# ak8975_i2c.net
KiCad netlist of a schematic drawn in Altium Designer
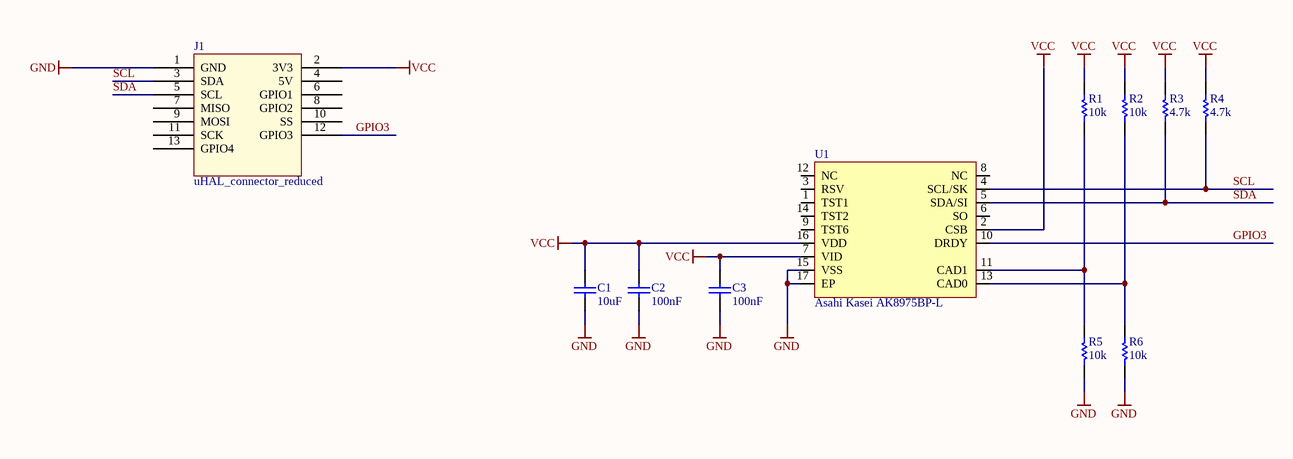
[diagram p0: ak8975_i2c.SchDoc]

(export (version "E")
  (design (tool "Eeschema 10.0.6"))
  (components
    (comp (ref "C1")
      (value "Murata GCM188R71H104KA57D")
      (footprint "CAPC1608X90X35ML10T15")
      (description "CAP CER 0.1UF 50V 10% X7R 0603")
      (fields (field (name "CAPACITANCE") "10uF"))
      (libsource (lib "CommunityVault") (part "CMP-119667-3"))
    )
    (comp (ref "C2")
      (value "Murata GCM188R71H104KA57D")
      (footprint "CAPC1608X90X35ML10T15")
      (description "CAP CER 0.1UF 50V 10% X7R 0603")
      (fields (field (name "CAPACITANCE") "100nF"))
      (libsource (lib "CommunityVault") (part "CMP-119667-3"))
    )
    (comp (ref "C3")
      (value "Murata GCM188R71H104KA57D")
      (footprint "CAPC1608X90X35ML10T15")
      (description "CAP CER 0.1UF 50V 10% X7R 0603")
      (fields (field (name "CAPACITANCE") "100nF"))
      (libsource (lib "CommunityVault") (part "CMP-119667-3"))
    )
    (comp (ref "J1")
      (value "uHAL_connector_reduced")
      (footprint "PCB-45ncoppm4oopozvqifsq-1")
      (description "connector for uHAL with reduced pin number")
      (libsource (lib "CommunityVault") (part "CMP-2q23h2cwhjlfm8s6r7i8-1"))
    )
    (comp (ref "R1")
      (value "10k")
      (footprint "RESC1608X05N")
      (description "RCA Series 0603 0.1 W 0 O Jumper Surface Mount Thick Film Chip Resistor")
      (fields (field (name "MANUFACTURER PART NUMBER") "RCA06030000ZSEA"))
      (libsource (lib "CommunityVault") (part "SYM-31acf99032f6ee6b-1"))
    )
    (comp (ref "R2")
      (value "10k")
      (footprint "RESC1608X05N")
      (description "RCA Series 0603 0.1 W 0 O Jumper Surface Mount Thick Film Chip Resistor")
      (fields (field (name "MANUFACTURER PART NUMBER") "RCA06030000ZSEA"))
      (libsource (lib "CommunityVault") (part "SYM-31acf99032f6ee6b-1"))
    )
    (comp (ref "R3")
      (value "4.7k")
      (footprint "RESC1608X05N")
      (description "RCA Series 0603 0.1 W 0 O Jumper Surface Mount Thick Film Chip Resistor")
      (fields (field (name "MANUFACTURER PART NUMBER") "RCA06030000ZSEA"))
      (libsource (lib "CommunityVault") (part "SYM-31acf99032f6ee6b-1"))
    )
    (comp (ref "R4")
      (value "4.7k")
      (footprint "RESC1608X05N")
      (description "RCA Series 0603 0.1 W 0 O Jumper Surface Mount Thick Film Chip Resistor")
      (fields (field (name "MANUFACTURER PART NUMBER") "RCA06030000ZSEA"))
      (libsource (lib "CommunityVault") (part "SYM-31acf99032f6ee6b-1"))
    )
    (comp (ref "R5")
      (value "10k")
      (footprint "RESC1608X05N")
      (description "RCA Series 0603 0.1 W 0 O Jumper Surface Mount Thick Film Chip Resistor")
      (fields (field (name "MANUFACTURER PART NUMBER") "RCA06030000ZSEA"))
      (libsource (lib "CommunityVault") (part "SYM-31acf99032f6ee6b-1"))
    )
    (comp (ref "R6")
      (value "10k")
      (footprint "RESC1608X05N")
      (description "RCA Series 0603 0.1 W 0 O Jumper Surface Mount Thick Film Chip Resistor")
      (fields (field (name "MANUFACTURER PART NUMBER") "RCA06030000ZSEA"))
      (libsource (lib "CommunityVault") (part "SYM-31acf99032f6ee6b-1"))
    )
    (comp (ref "U1")
      (value "Asahi Kasei AK8975BP-L")
      (footprint "PCB-e1nx98ugchmxbk2nqwbe-1")
      (description "3-axis Electronic Compass")
      (fields (field (name "MANUFACTURER PART NUMBER") "AK8975BP-L"))
      (libsource (lib "CommunityVault") (part "CMP-3b1ff0b150b6e4d8-1"))
    )
  )
  (nets
    (net (code "1") (name "/GPIO3") (class "Default")
      (node (ref "J1") (pin "12") (pinfunction "GPIO3_12") (pintype "passive"))
      (node (ref "U1") (pin "10") (pinfunction "DRDY_10") (pintype "power_in"))
    )
    (net (code "2") (name "/SCL") (class "Default")
      (node (ref "J1") (pin "3") (pinfunction "SDA_3") (pintype "passive"))
      (node (ref "R4") (pin "1") (pinfunction "1_1") (pintype "passive"))
      (node (ref "U1") (pin "4") (pinfunction "SCL/SK_4") (pintype "power_in"))
    )
    (net (code "3") (name "/SDA") (class "Default")
      (node (ref "J1") (pin "5") (pinfunction "SCL_5") (pintype "passive"))
      (node (ref "R3") (pin "1") (pinfunction "1_1") (pintype "passive"))
      (node (ref "U1") (pin "5") (pinfunction "SDA/SI_5") (pintype "power_in"))
    )
    (net (code "4") (name "GND") (class "Default")
      (node (ref "C1") (pin "2") (pinfunction "2_2") (pintype "passive"))
      (node (ref "C2") (pin "2") (pinfunction "2_2") (pintype "passive"))
      (node (ref "C3") (pin "2") (pinfunction "2_2") (pintype "passive"))
      (node (ref "J1") (pin "1") (pinfunction "GND_1") (pintype "passive"))
      (node (ref "R5") (pin "1") (pinfunction "1_1") (pintype "passive"))
      (node (ref "R6") (pin "1") (pinfunction "1_1") (pintype "passive"))
      (node (ref "U1") (pin "15") (pinfunction "VSS_15") (pintype "power_in"))
      (node (ref "U1") (pin "17") (pinfunction "EP_17") (pintype "power_in"))
    )
    (net (code "5") (name "Net-(U1-CAD0)") (class "Default")
      (node (ref "R2") (pin "1") (pinfunction "1_1") (pintype "passive"))
      (node (ref "R6") (pin "2") (pinfunction "2_2") (pintype "passive"))
      (node (ref "U1") (pin "13") (pinfunction "CAD0_13") (pintype "power_in"))
    )
    (net (code "6") (name "Net-(U1-CAD1)") (class "Default")
      (node (ref "R1") (pin "1") (pinfunction "1_1") (pintype "passive"))
      (node (ref "R5") (pin "2") (pinfunction "2_2") (pintype "passive"))
      (node (ref "U1") (pin "11") (pinfunction "CAD1_11") (pintype "power_in"))
    )
    (net (code "7") (name "VCC") (class "Default")
      (node (ref "C1") (pin "1") (pinfunction "1_1") (pintype "passive"))
      (node (ref "C2") (pin "1") (pinfunction "1_1") (pintype "passive"))
      (node (ref "C3") (pin "1") (pinfunction "1_1") (pintype "passive"))
      (node (ref "J1") (pin "2") (pinfunction "3V3_2") (pintype "passive"))
      (node (ref "R1") (pin "2") (pinfunction "2_2") (pintype "passive"))
      (node (ref "R2") (pin "2") (pinfunction "2_2") (pintype "passive"))
      (node (ref "R3") (pin "2") (pinfunction "2_2") (pintype "passive"))
      (node (ref "R4") (pin "2") (pinfunction "2_2") (pintype "passive"))
      (node (ref "U1") (pin "16") (pinfunction "VDD_16") (pintype "power_in"))
      (node (ref "U1") (pin "2") (pinfunction "CSB_2") (pintype "power_in"))
      (node (ref "U1") (pin "7") (pinfunction "VID_7") (pintype "power_in"))
    )
    (net (code "8") (name "unconnected-(J1-5V-Pad4)") (class "Default")
      (node (ref "J1") (pin "4") (pinfunction "5V_4") (pintype "passive"))
    )
    (net (code "9") (name "unconnected-(J1-GPIO1-Pad6)") (class "Default")
      (node (ref "J1") (pin "6") (pinfunction "GPIO1_6") (pintype "passive"))
    )
    (net (code "10") (name "unconnected-(J1-GPIO2-Pad8)") (class "Default")
      (node (ref "J1") (pin "8") (pinfunction "GPIO2_8") (pintype "passive"))
    )
    (net (code "11") (name "unconnected-(J1-GPIO4-Pad13)") (class "Default")
      (node (ref "J1") (pin "13") (pinfunction "GPIO4_13") (pintype "passive"))
    )
    (net (code "12") (name "unconnected-(J1-MISO-Pad7)") (class "Default")
      (node (ref "J1") (pin "7") (pinfunction "MISO_7") (pintype "passive"))
    )
    (net (code "13") (name "unconnected-(J1-MOSI-Pad9)") (class "Default")
      (node (ref "J1") (pin "9") (pinfunction "MOSI_9") (pintype "passive"))
    )
    (net (code "14") (name "unconnected-(J1-SCK-Pad11)") (class "Default")
      (node (ref "J1") (pin "11") (pinfunction "SCK_11") (pintype "passive"))
    )
    (net (code "15") (name "unconnected-(J1-SS-Pad10)") (class "Default")
      (node (ref "J1") (pin "10") (pinfunction "SS_10") (pintype "passive"))
    )
    (net (code "16") (name "unconnected-(U1-NC-Pad8)") (class "Default")
      (node (ref "U1") (pin "8") (pinfunction "NC_8") (pintype "power_in"))
    )
    (net (code "17") (name "unconnected-(U1-NC-Pad12)") (class "Default")
      (node (ref "U1") (pin "12") (pinfunction "NC_12") (pintype "power_in"))
    )
    (net (code "18") (name "unconnected-(U1-RSV-Pad3)") (class "Default")
      (node (ref "U1") (pin "3") (pinfunction "RSV_3") (pintype "power_in"))
    )
    (net (code "19") (name "unconnected-(U1-SO-Pad6)") (class "Default")
      (node (ref "U1") (pin "6") (pinfunction "SO_6") (pintype "power_in"))
    )
    (net (code "20") (name "unconnected-(U1-TST1-Pad1)") (class "Default")
      (node (ref "U1") (pin "1") (pinfunction "TST1_1") (pintype "power_in"))
    )
    (net (code "21") (name "unconnected-(U1-TST2-Pad14)") (class "Default")
      (node (ref "U1") (pin "14") (pinfunction "TST2_14") (pintype "power_in"))
    )
    (net (code "22") (name "unconnected-(U1-TST6-Pad9)") (class "Default")
      (node (ref "U1") (pin "9") (pinfunction "TST6_9") (pintype "power_in"))
    )
  )
)
